# Strain-TI.net
KiCad netlist of a schematic drawn in Altium Designer
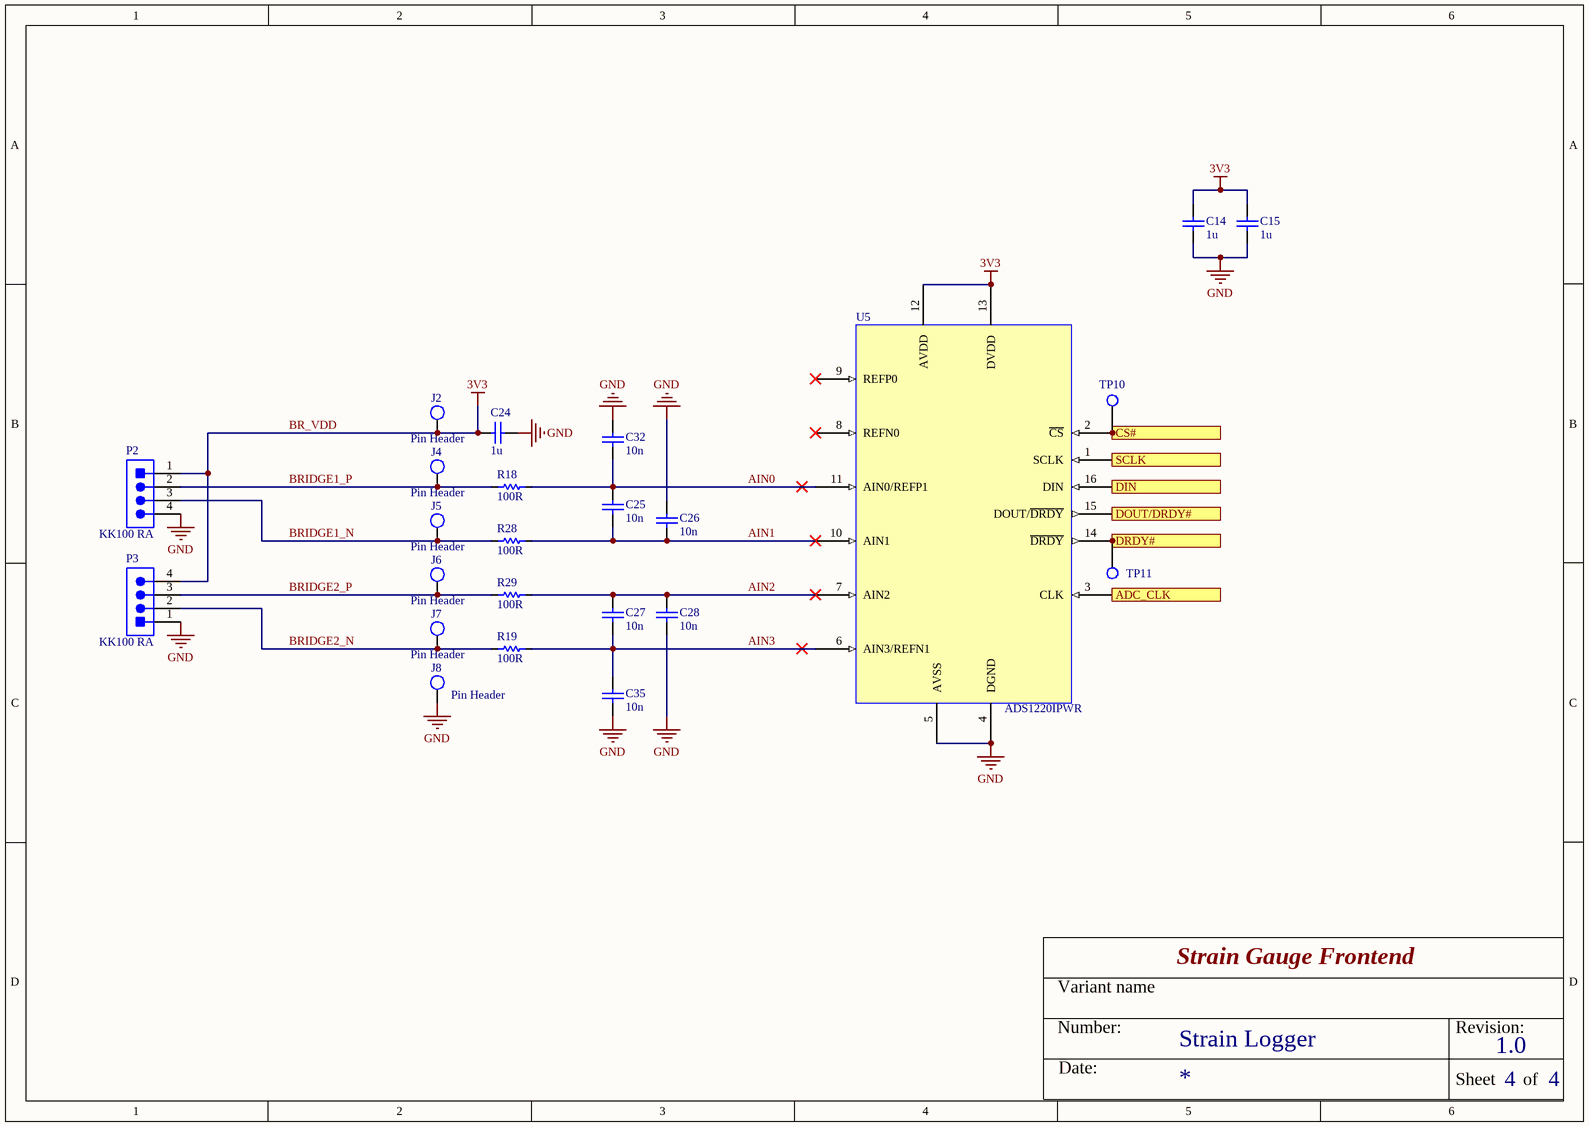
[diagram p0: Strain-TI.SchDoc]

(export (version "E")
  (design (tool "Eeschema 10.0.6"))
  (components
    (comp (ref "C14")
      (value "1u")
      (footprint "CAP_0603_M")
      (description "CAP 1uF 6.3V 20% X7R 0603")
      (fields (field (name "CREATED BY") "JS"))
      (libsource (lib "Passives") (part "CAP_0603"))
    )
    (comp (ref "C15")
      (value "1u")
      (footprint "CAP_0603_M")
      (description "CAP 1uF 6.3V 20% X7R 0603")
      (fields (field (name "CREATED BY") "JS"))
      (libsource (lib "Passives") (part "CAP_0603"))
    )
    (comp (ref "C24")
      (value "1u")
      (footprint "CAP_0603_M")
      (description "CAP 1uF 6.3V 20% X7R 0603")
      (fields (field (name "CREATED BY") "JS"))
      (libsource (lib "Passives") (part "CAP_0603"))
    )
    (comp (ref "C25")
      (value "10n")
      (footprint "CAP_0603_M")
      (description "CAP 10nF 6.3V 20% X7R 0603")
      (fields (field (name "CREATED BY") "JS"))
      (libsource (lib "Passives") (part "CAP_0603"))
    )
    (comp (ref "C26")
      (value "10n")
      (footprint "CAP_0603_M")
      (description "CAP 10nF 6.3V 20% X7R 0603")
      (fields (field (name "CREATED BY") "JS"))
      (libsource (lib "Passives") (part "CAP_0603"))
    )
    (comp (ref "C27")
      (value "10n")
      (footprint "CAP_0603_M")
      (description "CAP 10nF 6.3V 20% X7R 0603")
      (fields (field (name "CREATED BY") "JS"))
      (libsource (lib "Passives") (part "CAP_0603"))
    )
    (comp (ref "C28")
      (value "10n")
      (footprint "CAP_0603_M")
      (description "CAP 10nF 6.3V 20% X7R 0603")
      (fields (field (name "CREATED BY") "JS"))
      (libsource (lib "Passives") (part "CAP_0603"))
    )
    (comp (ref "C32")
      (value "10n")
      (footprint "CAP_0603_M")
      (description "CAP 10nF 6.3V 20% X7R 0603")
      (fields (field (name "CREATED BY") "JS"))
      (libsource (lib "Passives") (part "CAP_0603"))
    )
    (comp (ref "C35")
      (value "10n")
      (footprint "CAP_0603_M")
      (description "CAP 10nF 6.3V 20% X7R 0603")
      (fields (field (name "CREATED BY") "JS"))
      (libsource (lib "Passives") (part "CAP_0603"))
    )
    (comp (ref "J2")
      (value "Pin Header")
      (footprint "PIN_HEADER_1POS")
      (description "Pin Header 0.1\" 1pos")
      (libsource (lib "Connectors") (part "PIN_HEADER_1POS"))
    )
    (comp (ref "J4")
      (value "Pin Header")
      (footprint "PIN_HEADER_1POS")
      (description "Pin Header 0.1\" 1pos")
      (libsource (lib "Connectors") (part "PIN_HEADER_1POS"))
    )
    (comp (ref "J5")
      (value "Pin Header")
      (footprint "PIN_HEADER_1POS")
      (description "Pin Header 0.1\" 1pos")
      (libsource (lib "Connectors") (part "PIN_HEADER_1POS"))
    )
    (comp (ref "J6")
      (value "Pin Header")
      (footprint "PIN_HEADER_1POS")
      (description "Pin Header 0.1\" 1pos")
      (libsource (lib "Connectors") (part "PIN_HEADER_1POS"))
    )
    (comp (ref "J7")
      (value "Pin Header")
      (footprint "PIN_HEADER_1POS")
      (description "Pin Header 0.1\" 1pos")
      (libsource (lib "Connectors") (part "PIN_HEADER_1POS"))
    )
    (comp (ref "J8")
      (value "Pin Header")
      (footprint "PIN_HEADER_1POS")
      (description "Pin Header 0.1\" 1pos")
      (libsource (lib "Connectors") (part "PIN_HEADER_1POS"))
    )
    (comp (ref "P2")
      (value "KK100 RA")
      (footprint "MOLEX_KK100_RA_4P")
      (description "Right angle rectangular connector, KK100, 4pos")
      (fields (field (name "MANUFACTURER") "Molex"))
      (libsource (lib "") (part "MOLEX_KK100_RA_4P_1"))
    )
    (comp (ref "P3")
      (value "KK100 RA")
      (footprint "MOLEX_KK100_RA_4P")
      (description "Right angle rectangular connector, KK100, 4pos")
      (fields (field (name "MANUFACTURER") "Molex"))
      (libsource (lib "Connectors") (part "MOLEX_KK100_RA_4P"))
    )
    (comp (ref "R18")
      (value "100R")
      (footprint "RES_0603_M")
      (description "RES 100R 1/5W 0603")
      (fields (field (name "CREATED BY") "JS"))
      (libsource (lib "Passives") (part "RES_0603"))
    )
    (comp (ref "R19")
      (value "100R")
      (footprint "RES_0603_M")
      (description "RES 100R 1/5W 0603")
      (fields (field (name "CREATED BY") "JS"))
      (libsource (lib "Passives") (part "RES_0603"))
    )
    (comp (ref "R28")
      (value "100R")
      (footprint "RES_0603_M")
      (description "RES 100R 1/5W 0603")
      (fields (field (name "CREATED BY") "JS"))
      (libsource (lib "Passives") (part "RES_0603"))
    )
    (comp (ref "R29")
      (value "100R")
      (footprint "RES_0603_M")
      (description "RES 100R 1/5W 0603")
      (fields (field (name "CREATED BY") "JS"))
      (libsource (lib "Passives") (part "RES_0603"))
    )
    (comp (ref "TP10")
      (value "TP-1.5mm")
      (footprint "TP-1.5mm")
      (description "Test Point")
      (libsource (lib "Connectors") (part "TP-1.5mm"))
    )
    (comp (ref "TP11")
      (value "TP-1.5mm")
      (footprint "TP-1.5mm")
      (description "Test Point")
      (libsource (lib "Connectors") (part "TP-1.5mm"))
    )
    (comp (ref "U5")
      (value "ADS1220IPWR")
      (footprint "TI_PW_SOP127P600-8N")
      (description "ADS1220 4-Channel, 2-kSPS, Low-Power, 24-Bit ADC with Integrated PGA and Reference")
      (fields (field (name "MANUFACTURER") "TI"))
      (libsource (lib "IC") (part "TI_ADS1220IPWR"))
    )
  )
  (nets
    (net (code "1") (name "/ADC_CLK") (class "Default")
      (node (ref "U5") (pin "3") (pinfunction "CLK_3") (pintype "input"))
    )
    (net (code "2") (name "/AIN0") (class "Default")
      (node (ref "C25") (pin "2") (pinfunction "2_2") (pintype "passive"))
      (node (ref "C32") (pin "1") (pinfunction "1_1") (pintype "passive"))
      (node (ref "R18") (pin "2") (pinfunction "2_2") (pintype "passive"))
      (node (ref "U5") (pin "11") (pinfunction "AIN0/REFP1_11") (pintype "input"))
    )
    (net (code "3") (name "/AIN1") (class "Default")
      (node (ref "C25") (pin "1") (pinfunction "1_1") (pintype "passive"))
      (node (ref "C26") (pin "1") (pinfunction "1_1") (pintype "passive"))
      (node (ref "R28") (pin "2") (pinfunction "2_2") (pintype "passive"))
      (node (ref "U5") (pin "10") (pinfunction "AIN1_10") (pintype "input"))
    )
    (net (code "4") (name "/AIN2") (class "Default")
      (node (ref "C27") (pin "2") (pinfunction "2_2") (pintype "passive"))
      (node (ref "C28") (pin "1") (pinfunction "1_1") (pintype "passive"))
      (node (ref "R29") (pin "2") (pinfunction "2_2") (pintype "passive"))
      (node (ref "U5") (pin "7") (pinfunction "AIN2_7") (pintype "input"))
    )
    (net (code "5") (name "/AIN3") (class "Default")
      (node (ref "C27") (pin "1") (pinfunction "1_1") (pintype "passive"))
      (node (ref "C35") (pin "2") (pinfunction "2_2") (pintype "passive"))
      (node (ref "R19") (pin "2") (pinfunction "2_2") (pintype "passive"))
      (node (ref "U5") (pin "6") (pinfunction "AIN3/REFN1_6") (pintype "input"))
    )
    (net (code "6") (name "/BRIDGE1_N") (class "Default")
      (node (ref "J5") (pin "1") (pinfunction "1_1") (pintype "passive"))
      (node (ref "P2") (pin "3") (pinfunction "3_3") (pintype "passive"))
      (node (ref "R28") (pin "1") (pinfunction "1_1") (pintype "passive"))
    )
    (net (code "7") (name "/BRIDGE1_P") (class "Default")
      (node (ref "J4") (pin "1") (pinfunction "1_1") (pintype "passive"))
      (node (ref "P2") (pin "2") (pinfunction "2_2") (pintype "passive"))
      (node (ref "R18") (pin "1") (pinfunction "1_1") (pintype "passive"))
    )
    (net (code "8") (name "/BRIDGE2_N") (class "Default")
      (node (ref "J7") (pin "1") (pinfunction "1_1") (pintype "passive"))
      (node (ref "P3") (pin "2") (pinfunction "2_2") (pintype "passive"))
      (node (ref "R19") (pin "1") (pinfunction "1_1") (pintype "passive"))
    )
    (net (code "9") (name "/BRIDGE2_P") (class "Default")
      (node (ref "J6") (pin "1") (pinfunction "1_1") (pintype "passive"))
      (node (ref "P3") (pin "3") (pinfunction "3_3") (pintype "passive"))
      (node (ref "R29") (pin "1") (pinfunction "1_1") (pintype "passive"))
    )
    (net (code "10") (name "/CS#") (class "Default")
      (node (ref "TP10") (pin "1") (pinfunction "1_1") (pintype "passive"))
      (node (ref "U5") (pin "2") (pinfunction "~{CS}_2") (pintype "input"))
    )
    (net (code "11") (name "/DIN") (class "Default")
      (node (ref "U5") (pin "16") (pinfunction "DIN_16") (pintype "input"))
    )
    (net (code "12") (name "/DOUT{slash}DRDY#") (class "Default")
      (node (ref "U5") (pin "15") (pinfunction "DOUT/~{DRDY}_15") (pintype "output"))
    )
    (net (code "13") (name "/DRDY#") (class "Default")
      (node (ref "TP11") (pin "1") (pinfunction "1_1") (pintype "passive"))
      (node (ref "U5") (pin "14") (pinfunction "~{DRDY}_14") (pintype "output"))
    )
    (net (code "14") (name "/SCLK") (class "Default")
      (node (ref "U5") (pin "1") (pinfunction "SCLK_1") (pintype "input"))
    )
    (net (code "15") (name "3V3") (class "Default")
      (node (ref "C14") (pin "2") (pinfunction "2_2") (pintype "passive"))
      (node (ref "C15") (pin "2") (pinfunction "2_2") (pintype "passive"))
      (node (ref "C24") (pin "1") (pinfunction "1_1") (pintype "passive"))
      (node (ref "J2") (pin "1") (pinfunction "1_1") (pintype "passive"))
      (node (ref "P2") (pin "1") (pinfunction "1_1") (pintype "passive"))
      (node (ref "P3") (pin "4") (pinfunction "4_4") (pintype "passive"))
      (node (ref "U5") (pin "12") (pinfunction "AVDD_12") (pintype "power_in"))
      (node (ref "U5") (pin "13") (pinfunction "DVDD_13") (pintype "power_in"))
    )
    (net (code "16") (name "GND") (class "Default")
      (node (ref "C14") (pin "1") (pinfunction "1_1") (pintype "passive"))
      (node (ref "C15") (pin "1") (pinfunction "1_1") (pintype "passive"))
      (node (ref "C24") (pin "2") (pinfunction "2_2") (pintype "passive"))
      (node (ref "C26") (pin "2") (pinfunction "2_2") (pintype "passive"))
      (node (ref "C28") (pin "2") (pinfunction "2_2") (pintype "passive"))
      (node (ref "C32") (pin "2") (pinfunction "2_2") (pintype "passive"))
      (node (ref "C35") (pin "1") (pinfunction "1_1") (pintype "passive"))
      (node (ref "J8") (pin "1") (pinfunction "1_1") (pintype "passive"))
      (node (ref "P2") (pin "4") (pinfunction "4_4") (pintype "passive"))
      (node (ref "P3") (pin "1") (pinfunction "1_1") (pintype "passive"))
      (node (ref "U5") (pin "4") (pinfunction "DGND_4") (pintype "power_in"))
      (node (ref "U5") (pin "5") (pinfunction "AVSS_5") (pintype "power_in"))
    )
    (net (code "17") (name "unconnected-(U5-REFN0-Pad8)") (class "Default")
      (node (ref "U5") (pin "8") (pinfunction "REFN0_8") (pintype "input+no_connect"))
    )
    (net (code "18") (name "unconnected-(U5-REFP0-Pad9)") (class "Default")
      (node (ref "U5") (pin "9") (pinfunction "REFP0_9") (pintype "input+no_connect"))
    )
  )
)
